# SCH_M5_GreenHat_Coil_Driver_2021-08-27.net
KiCad netlist of a schematic drawn in EasyEDA
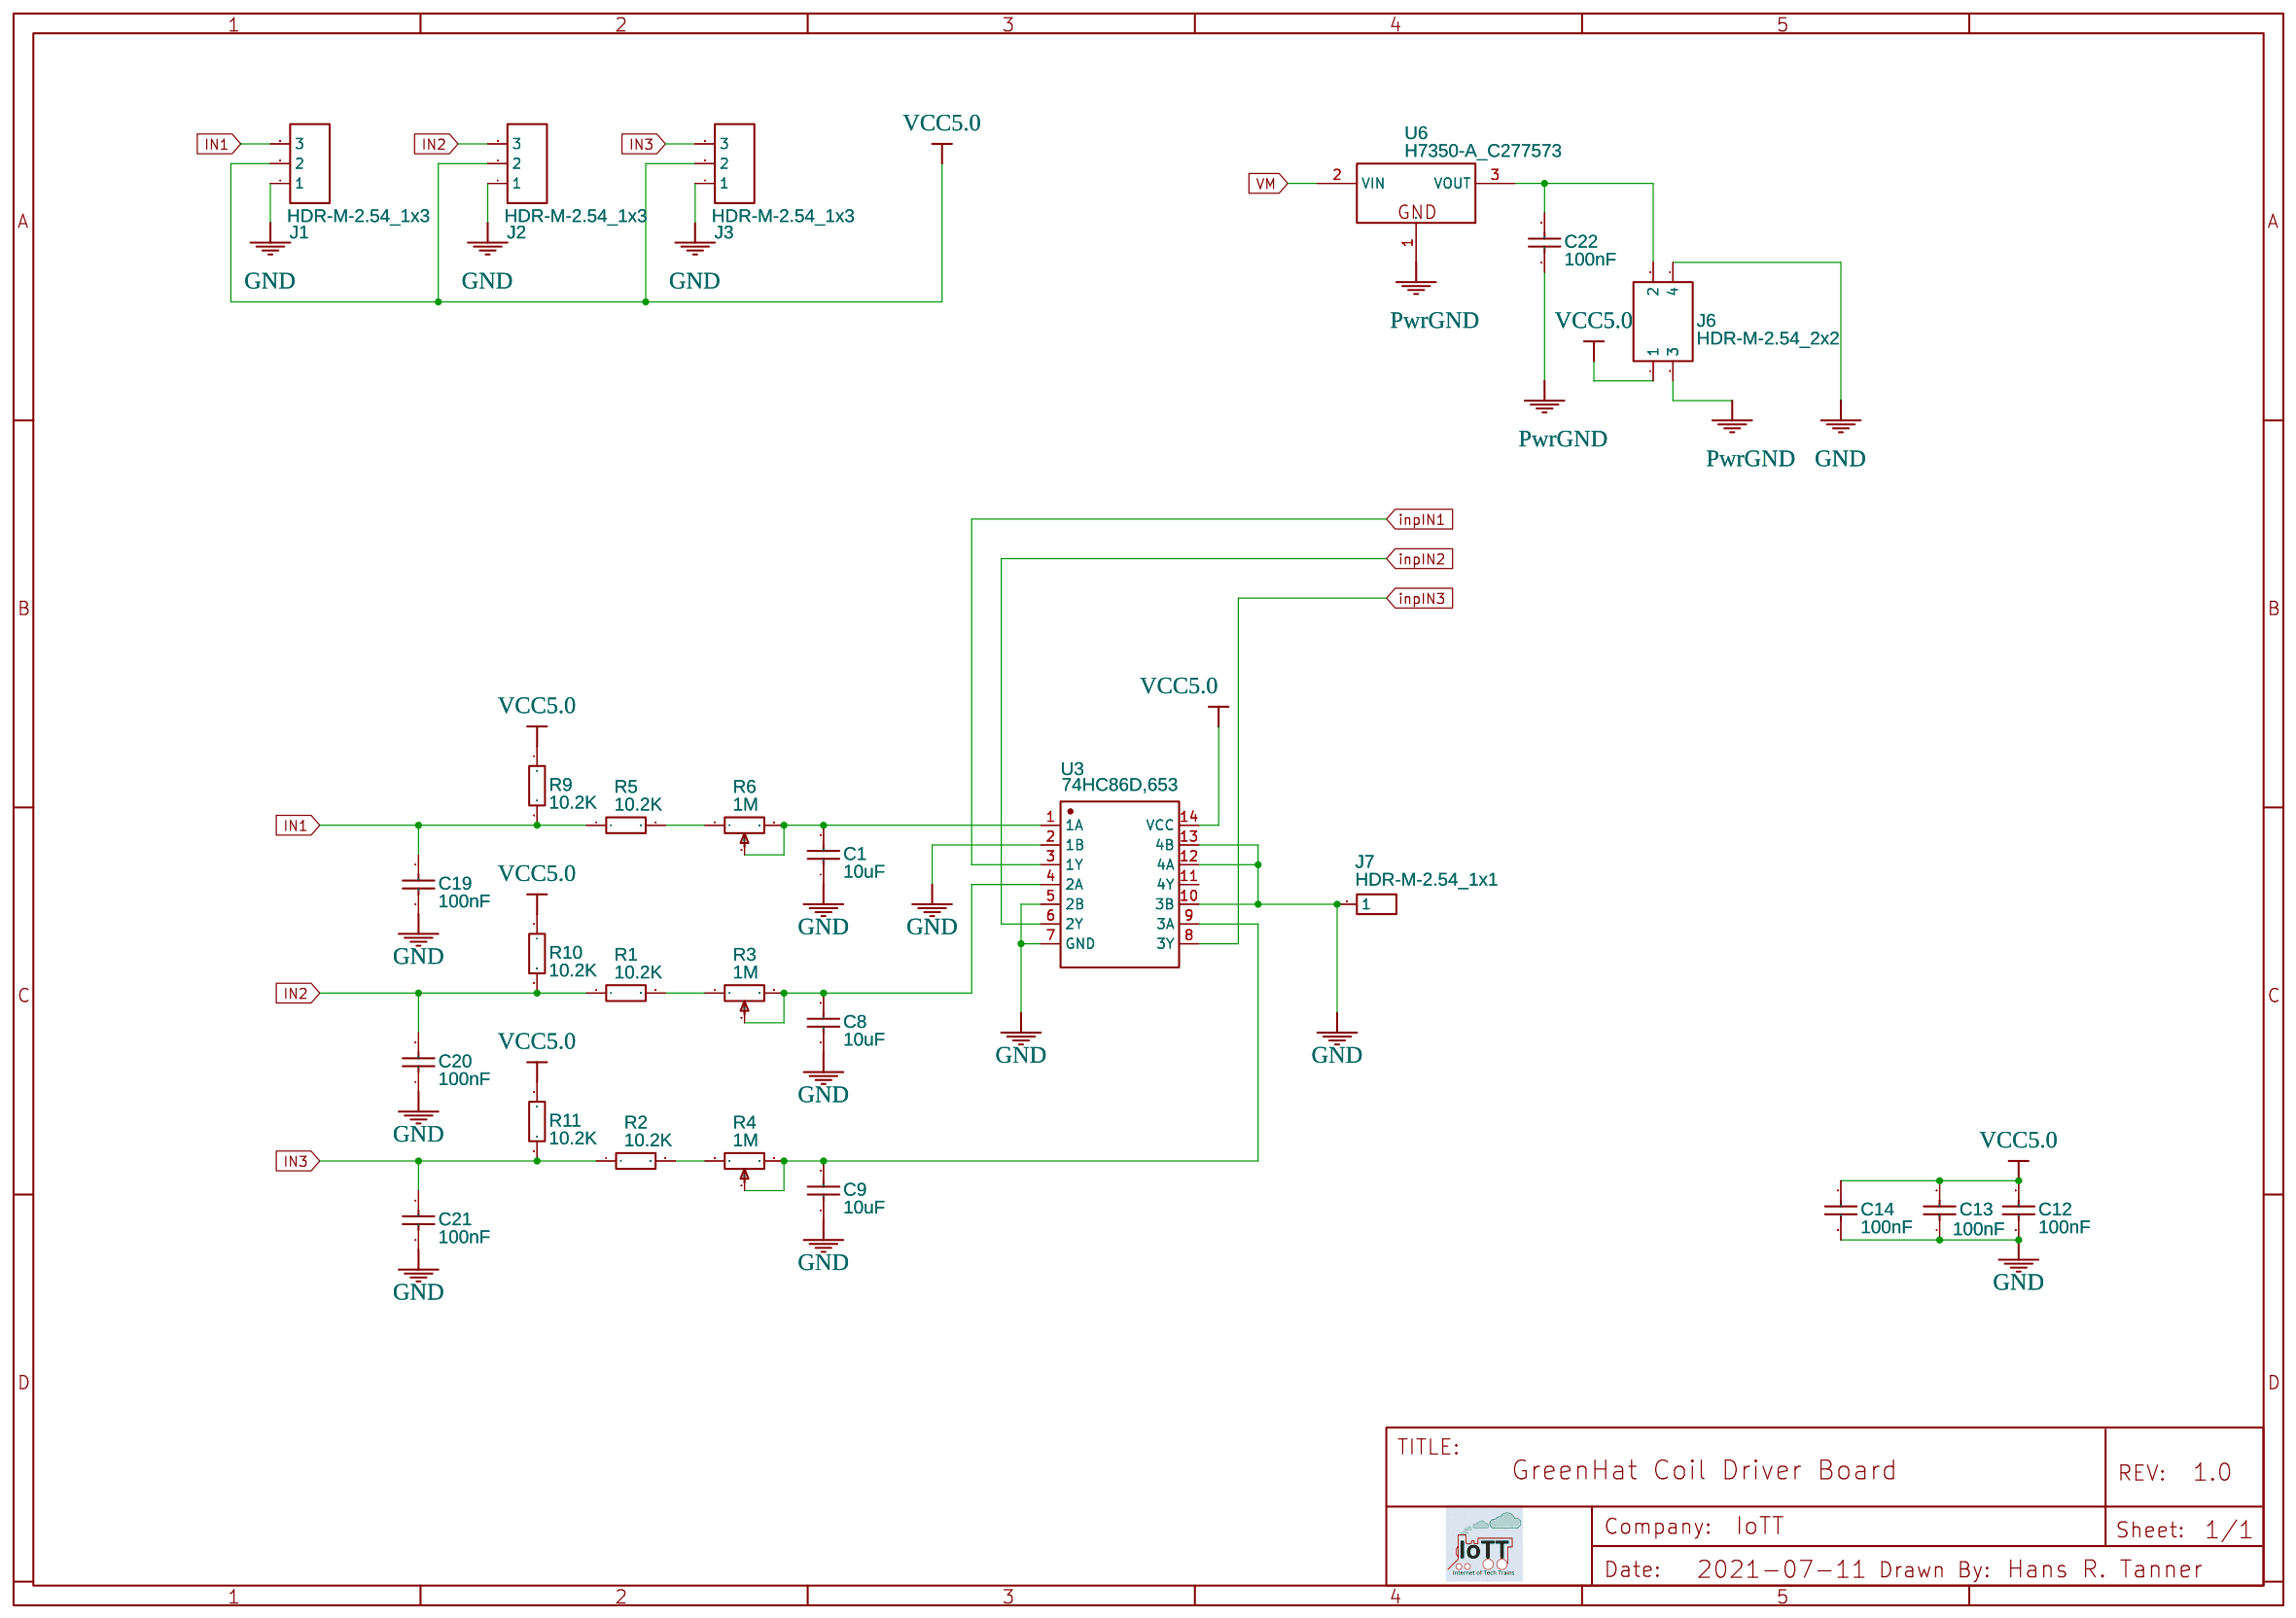
[diagram p0: Input Logic]
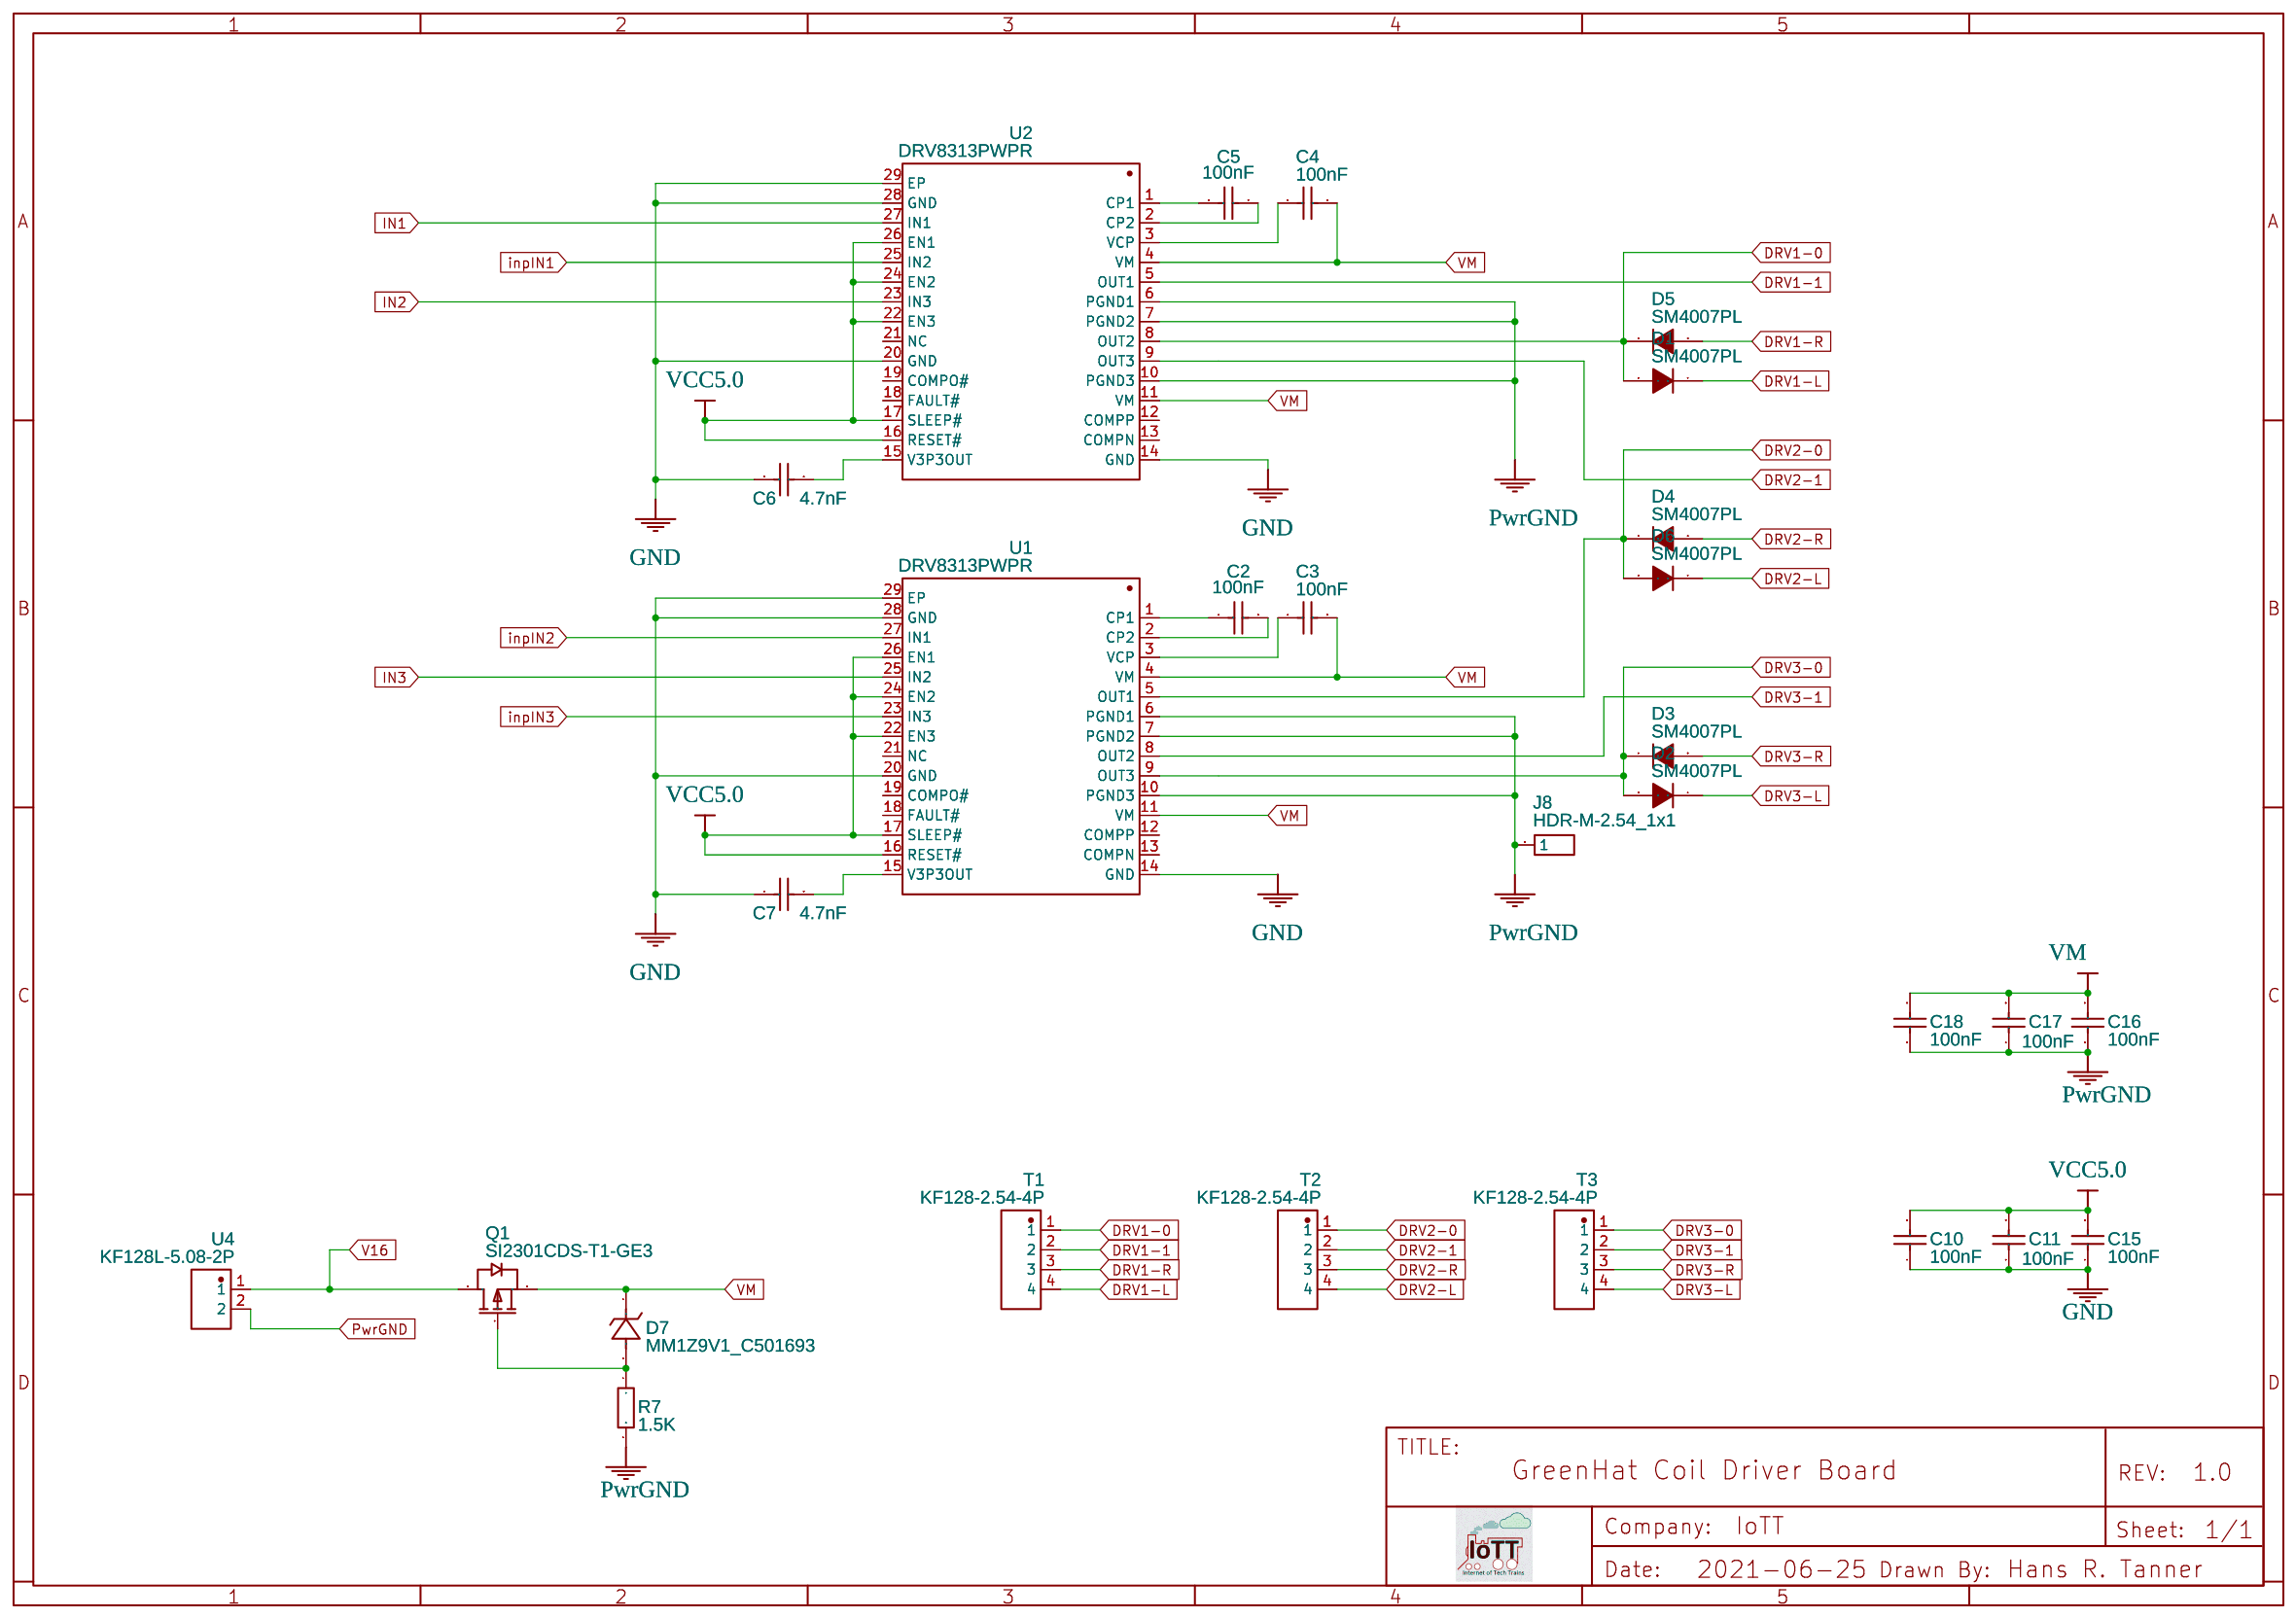
[diagram p1: Bridge]

(export (version "E")
  (design (tool "Eeschema 10.0.6"))
  (components
    (comp (ref "C1")
      (value "10uF")
      (fields
        (field (name "BOM_Manufacturer Part") "CL21A106KAYNNNE")
        (field (name "BOM_Supplier Part") "C15850")
      )
      (libsource (lib "") (part "CL21A106KAYNNNE"))
    )
    (comp (ref "C8")
      (value "10uF")
      (fields
        (field (name "BOM_Manufacturer Part") "CL21A106KAYNNNE")
        (field (name "BOM_Supplier Part") "C15850")
      )
      (libsource (lib "") (part "CL21A106KAYNNNE"))
    )
    (comp (ref "C9")
      (value "10uF")
      (fields
        (field (name "BOM_Manufacturer Part") "CL21A106KAYNNNE")
        (field (name "BOM_Supplier Part") "C15850")
      )
      (libsource (lib "") (part "CL21A106KAYNNNE"))
    )
    (comp (ref "C12")
      (value "100nF")
      (fields
        (field (name "BOM_Manufacturer Part") "CL05B104KO5NNNC")
        (field (name "BOM_Supplier Part") "C1525")
      )
      (libsource (lib "") (part "CL05B104KO5NNNC"))
    )
    (comp (ref "C13")
      (value "100nF")
      (fields
        (field (name "BOM_Manufacturer Part") "CL05B104KO5NNNC")
        (field (name "BOM_Supplier Part") "C1525")
      )
      (libsource (lib "") (part "CL05B104KO5NNNC"))
    )
    (comp (ref "C14")
      (value "100nF")
      (fields
        (field (name "BOM_Manufacturer Part") "CL05B104KO5NNNC")
        (field (name "BOM_Supplier Part") "C1525")
      )
      (libsource (lib "") (part "CL05B104KO5NNNC"))
    )
    (comp (ref "C19")
      (value "100nF")
      (fields
        (field (name "BOM_Manufacturer Part") "CL05B104KO5NNNC")
        (field (name "BOM_Supplier Part") "C1525")
      )
      (libsource (lib "") (part "CL05B104KO5NNNC"))
    )
    (comp (ref "C20")
      (value "100nF")
      (fields
        (field (name "BOM_Manufacturer Part") "CL05B104KO5NNNC")
        (field (name "BOM_Supplier Part") "C1525")
      )
      (libsource (lib "") (part "CL05B104KO5NNNC"))
    )
    (comp (ref "C21")
      (value "100nF")
      (fields
        (field (name "BOM_Manufacturer Part") "CL05B104KO5NNNC")
        (field (name "BOM_Supplier Part") "C1525")
      )
      (libsource (lib "") (part "CL05B104KO5NNNC"))
    )
    (comp (ref "C22")
      (value "100nF")
      (fields
        (field (name "BOM_Manufacturer Part") "CL05B104KO5NNNC")
        (field (name "BOM_Supplier Part") "C1525")
      )
      (libsource (lib "") (part "CL05B104KO5NNNC"))
    )
    (comp (ref "J1")
      (value "HDR-M-2.54_1x3")
      (fields (field (name "BOM_Supplier Part") "C180248"))
      (libsource (lib "") (part "HDR-M-2.54_1x3"))
    )
    (comp (ref "J2")
      (value "HDR-M-2.54_1x3")
      (fields (field (name "BOM_Supplier Part") "C180248"))
      (libsource (lib "") (part "HDR-M-2.54_1x3"))
    )
    (comp (ref "J3")
      (value "HDR-M-2.54_1x3")
      (fields (field (name "BOM_Supplier Part") "C180248"))
      (libsource (lib "") (part "HDR-M-2.54_1x3"))
    )
    (comp (ref "J6")
      (value "HDR-M-2.54_2x2")
      (fields (field (name "BOM_Supplier Part") "C66690"))
      (libsource (lib "") (part "HDR-M-2.54_2x2"))
    )
    (comp (ref "J7")
      (value "HDR-M-2.54_1x1")
      (fields (field (name "BOM_Supplier Part") "C81276"))
      (libsource (lib "") (part "HDR-M-2.54_1x1"))
    )
    (comp (ref "R1")
      (value "10.2K")
      (fields
        (field (name "BOM_Manufacturer Part") "RTT021022FTH")
        (field (name "BOM_Supplier Part") "C102756")
      )
      (libsource (lib "") (part "RTT021022FTH_1"))
    )
    (comp (ref "R2")
      (value "10.2K")
      (fields
        (field (name "BOM_Manufacturer Part") "RTT021022FTH")
        (field (name "BOM_Supplier Part") "C102756")
      )
      (libsource (lib "") (part "RTT021022FTH_1"))
    )
    (comp (ref "R3")
      (value "1M")
      (fields
        (field (name "BOM_Manufacturer Part") "3386P-1-105")
        (field (name "BOM_Supplier Part") "C118946")
      )
      (libsource (lib "") (part "3386P-1-105_C118946"))
    )
    (comp (ref "R4")
      (value "1M")
      (fields
        (field (name "BOM_Manufacturer Part") "3386P-1-105")
        (field (name "BOM_Supplier Part") "C118946")
      )
      (libsource (lib "") (part "3386P-1-105_C118946"))
    )
    (comp (ref "R5")
      (value "10.2K")
      (fields
        (field (name "BOM_Manufacturer Part") "RTT021022FTH")
        (field (name "BOM_Supplier Part") "C102756")
      )
      (libsource (lib "") (part "RTT021022FTH_1"))
    )
    (comp (ref "R6")
      (value "1M")
      (fields
        (field (name "BOM_Manufacturer Part") "3386P-1-105")
        (field (name "BOM_Supplier Part") "C118946")
      )
      (libsource (lib "") (part "3386P-1-105_C118946"))
    )
    (comp (ref "R9")
      (value "10.2K")
      (fields
        (field (name "BOM_Manufacturer Part") "RTT021022FTH")
        (field (name "BOM_Supplier Part") "C102756")
      )
      (libsource (lib "") (part "RTT021022FTH"))
    )
    (comp (ref "R10")
      (value "10.2K")
      (fields
        (field (name "BOM_Manufacturer Part") "RTT021022FTH")
        (field (name "BOM_Supplier Part") "C102756")
      )
      (libsource (lib "") (part "RTT021022FTH"))
    )
    (comp (ref "R11")
      (value "10.2K")
      (fields
        (field (name "BOM_Manufacturer Part") "RTT021022FTH")
        (field (name "BOM_Supplier Part") "C102756")
      )
      (libsource (lib "") (part "RTT021022FTH"))
    )
    (comp (ref "U3")
      (value "74HC86D,653")
      (fields (field (name "BOM_Supplier Part") "C5955"))
      (libsource (lib "") (part "74HC86D,653"))
    )
    (comp (ref "U6")
      (value "H7350-A_C277573")
      (fields (field (name "BOM_Manufacturer Part") "H7350-A") (field (name "BOM_Supplier Part") "C277573"))
      (libsource (lib "") (part "H7350-A_C277573"))
    )
    (comp (ref "C2")
      (value "100nF")
      (fields
        (field (name "BOM_Manufacturer Part") "CL05B104KO5NNNC")
        (field (name "BOM_Supplier Part") "C1525")
      )
      (libsource (lib "") (part "CL05B104KO5NNNC"))
    )
    (comp (ref "C3")
      (value "100nF")
      (fields
        (field (name "BOM_Manufacturer Part") "CL05B104KO5NNNC")
        (field (name "BOM_Supplier Part") "C1525")
      )
      (libsource (lib "") (part "CL05B104KO5NNNC"))
    )
    (comp (ref "C4")
      (value "100nF")
      (fields
        (field (name "BOM_Manufacturer Part") "CL05B104KO5NNNC")
        (field (name "BOM_Supplier Part") "C1525")
      )
      (libsource (lib "") (part "CL05B104KO5NNNC"))
    )
    (comp (ref "C5")
      (value "100nF")
      (fields
        (field (name "BOM_Manufacturer Part") "CL05B104KO5NNNC")
        (field (name "BOM_Supplier Part") "C1525")
      )
      (libsource (lib "") (part "CL05B104KO5NNNC"))
    )
    (comp (ref "C6")
      (value "4.7nF")
      (fields
        (field (name "BOM_Manufacturer Part") "0402B472K500NT")
        (field (name "BOM_Supplier Part") "C1538")
      )
      (libsource (lib "") (part "0402B472K500NT"))
    )
    (comp (ref "C7")
      (value "4.7nF")
      (fields
        (field (name "BOM_Manufacturer Part") "0402B472K500NT")
        (field (name "BOM_Supplier Part") "C1538")
      )
      (libsource (lib "") (part "0402B472K500NT"))
    )
    (comp (ref "C10")
      (value "100nF")
      (fields
        (field (name "BOM_Manufacturer Part") "CL05B104KO5NNNC")
        (field (name "BOM_Supplier Part") "C1525")
      )
      (libsource (lib "") (part "CL05B104KO5NNNC_1"))
    )
    (comp (ref "C11")
      (value "100nF")
      (fields
        (field (name "BOM_Manufacturer Part") "CL05B104KO5NNNC")
        (field (name "BOM_Supplier Part") "C1525")
      )
      (libsource (lib "") (part "CL05B104KO5NNNC_1"))
    )
    (comp (ref "C15")
      (value "100nF")
      (fields
        (field (name "BOM_Manufacturer Part") "CL05B104KO5NNNC")
        (field (name "BOM_Supplier Part") "C1525")
      )
      (libsource (lib "") (part "CL05B104KO5NNNC_1"))
    )
    (comp (ref "C16")
      (value "100nF")
      (fields
        (field (name "BOM_Manufacturer Part") "CL05B104KO5NNNC")
        (field (name "BOM_Supplier Part") "C1525")
      )
      (libsource (lib "") (part "CL05B104KO5NNNC_1"))
    )
    (comp (ref "C17")
      (value "100nF")
      (fields
        (field (name "BOM_Manufacturer Part") "CL05B104KO5NNNC")
        (field (name "BOM_Supplier Part") "C1525")
      )
      (libsource (lib "") (part "CL05B104KO5NNNC_1"))
    )
    (comp (ref "C18")
      (value "100nF")
      (fields
        (field (name "BOM_Manufacturer Part") "CL05B104KO5NNNC")
        (field (name "BOM_Supplier Part") "C1525")
      )
      (libsource (lib "") (part "CL05B104KO5NNNC_1"))
    )
    (comp (ref "D1")
      (value "SM4007PL")
      (fields (field (name "BOM_Supplier Part") "C64898"))
      (libsource (lib "") (part "SM4007PL_1"))
    )
    (comp (ref "D2")
      (value "SM4007PL")
      (fields (field (name "BOM_Supplier Part") "C64898"))
      (libsource (lib "") (part "SM4007PL_1"))
    )
    (comp (ref "D3")
      (value "SM4007PL")
      (fields (field (name "BOM_Supplier Part") "C64898"))
      (libsource (lib "") (part "SM4007PL"))
    )
    (comp (ref "D4")
      (value "SM4007PL")
      (fields (field (name "BOM_Supplier Part") "C64898"))
      (libsource (lib "") (part "SM4007PL"))
    )
    (comp (ref "D5")
      (value "SM4007PL")
      (fields (field (name "BOM_Supplier Part") "C64898"))
      (libsource (lib "") (part "SM4007PL"))
    )
    (comp (ref "D6")
      (value "SM4007PL")
      (fields (field (name "BOM_Supplier Part") "C64898"))
      (libsource (lib "") (part "SM4007PL_1"))
    )
    (comp (ref "D7")
      (value "MM1Z9V1_C501693")
      (fields (field (name "BOM_Manufacturer Part") "MM1Z9V1") (field (name "BOM_Supplier Part") "C501693"))
      (libsource (lib "") (part "MM1Z9V1_C501693"))
    )
    (comp (ref "J8")
      (value "HDR-M-2.54_1x1")
      (fields (field (name "BOM_Supplier Part") "C81276"))
      (libsource (lib "") (part "HDR-M-2.54_1x1"))
    )
    (comp (ref "Q1")
      (value "SI2301CDS-T1-GE3")
      (fields (field (name "BOM_Supplier Part") "C10487"))
      (libsource (lib "") (part "SI2301CDS-T1-GE3"))
    )
    (comp (ref "R7")
      (value "1.5K")
      (fields
        (field (name "BOM_Manufacturer Part") "0402WGF1501TCE")
        (field (name "BOM_Supplier Part") "C25867")
      )
      (libsource (lib "") (part "0402WGF1501TCE"))
    )
    (comp (ref "T1")
      (value "KF128-2.54-4P")
      (fields (field (name "BOM_Supplier Part") "C474922"))
      (libsource (lib "") (part "KF128-2.54-4P"))
    )
    (comp (ref "T2")
      (value "KF128-2.54-4P")
      (fields (field (name "BOM_Supplier Part") "C474922"))
      (libsource (lib "") (part "KF128-2.54-4P"))
    )
    (comp (ref "T3")
      (value "KF128-2.54-4P")
      (fields (field (name "BOM_Supplier Part") "C474922"))
      (libsource (lib "") (part "KF128-2.54-4P"))
    )
    (comp (ref "U1")
      (value "DRV8313PWPR")
      (fields (field (name "BOM_Supplier Part") "C92482"))
      (libsource (lib "") (part "DRV8313PWPR"))
    )
    (comp (ref "U2")
      (value "DRV8313PWPR")
      (fields (field (name "BOM_Supplier Part") "C92482"))
      (libsource (lib "") (part "DRV8313PWPR"))
    )
    (comp (ref "U4")
      (value "KF128L-5.08-2P")
      (fields (field (name "BOM_Supplier Part") "C474940"))
      (libsource (lib "") (part "KF128L-5.08-2P"))
    )
  )
  (nets
    (net (code "1") (name "DRV1-0") (class "Default")
      (node (ref "D1") (pin "2") (pinfunction "A_2") (pintype "unspecified"))
      (node (ref "D5") (pin "1") (pinfunction "C_1") (pintype "unspecified"))
      (node (ref "T1") (pin "1") (pinfunction "1_1") (pintype "unspecified"))
      (node (ref "U2") (pin "8") (pinfunction "OUT2_8") (pintype "unspecified"))
    )
    (net (code "2") (name "DRV1-1") (class "Default")
      (node (ref "T1") (pin "2") (pinfunction "2_2") (pintype "unspecified"))
      (node (ref "U2") (pin "5") (pinfunction "OUT1_5") (pintype "unspecified"))
    )
    (net (code "3") (name "DRV1-L") (class "Default")
      (node (ref "D1") (pin "1") (pinfunction "C_1") (pintype "unspecified"))
      (node (ref "T1") (pin "4") (pinfunction "4_4") (pintype "unspecified"))
    )
    (net (code "4") (name "DRV1-R") (class "Default")
      (node (ref "D5") (pin "2") (pinfunction "A_2") (pintype "unspecified"))
      (node (ref "T1") (pin "3") (pinfunction "3_3") (pintype "unspecified"))
    )
    (net (code "5") (name "DRV2-0") (class "Default")
      (node (ref "D4") (pin "1") (pinfunction "C_1") (pintype "unspecified"))
      (node (ref "D6") (pin "2") (pinfunction "A_2") (pintype "unspecified"))
      (node (ref "T2") (pin "1") (pinfunction "1_1") (pintype "unspecified"))
      (node (ref "U1") (pin "5") (pinfunction "OUT1_5") (pintype "unspecified"))
    )
    (net (code "6") (name "DRV2-1") (class "Default")
      (node (ref "T2") (pin "2") (pinfunction "2_2") (pintype "unspecified"))
      (node (ref "U2") (pin "9") (pinfunction "OUT3_9") (pintype "unspecified"))
    )
    (net (code "7") (name "DRV2-L") (class "Default")
      (node (ref "D6") (pin "1") (pinfunction "C_1") (pintype "unspecified"))
      (node (ref "T2") (pin "4") (pinfunction "4_4") (pintype "unspecified"))
    )
    (net (code "8") (name "DRV2-R") (class "Default")
      (node (ref "D4") (pin "2") (pinfunction "A_2") (pintype "unspecified"))
      (node (ref "T2") (pin "3") (pinfunction "3_3") (pintype "unspecified"))
    )
    (net (code "9") (name "DRV3-0") (class "Default")
      (node (ref "D2") (pin "2") (pinfunction "A_2") (pintype "unspecified"))
      (node (ref "D3") (pin "1") (pinfunction "C_1") (pintype "unspecified"))
      (node (ref "T3") (pin "1") (pinfunction "1_1") (pintype "unspecified"))
      (node (ref "U1") (pin "9") (pinfunction "OUT3_9") (pintype "unspecified"))
    )
    (net (code "10") (name "DRV3-1") (class "Default")
      (node (ref "T3") (pin "2") (pinfunction "2_2") (pintype "unspecified"))
      (node (ref "U1") (pin "8") (pinfunction "OUT2_8") (pintype "unspecified"))
    )
    (net (code "11") (name "DRV3-L") (class "Default")
      (node (ref "D2") (pin "1") (pinfunction "C_1") (pintype "unspecified"))
      (node (ref "T3") (pin "4") (pinfunction "4_4") (pintype "unspecified"))
    )
    (net (code "12") (name "DRV3-R") (class "Default")
      (node (ref "D3") (pin "2") (pinfunction "A_2") (pintype "unspecified"))
      (node (ref "T3") (pin "3") (pinfunction "3_3") (pintype "unspecified"))
    )
    (net (code "13") (name "GND") (class "Default")
      (node (ref "C1") (pin "1") (pinfunction "1_1") (pintype "input"))
      (node (ref "C10") (pin "1") (pinfunction "1_1") (pintype "input"))
      (node (ref "C11") (pin "1") (pinfunction "1_1") (pintype "input"))
      (node (ref "C12") (pin "1") (pinfunction "1_1") (pintype "input"))
      (node (ref "C13") (pin "1") (pinfunction "1_1") (pintype "input"))
      (node (ref "C14") (pin "1") (pinfunction "1_1") (pintype "input"))
      (node (ref "C15") (pin "1") (pinfunction "1_1") (pintype "input"))
      (node (ref "C19") (pin "1") (pinfunction "1_1") (pintype "input"))
      (node (ref "C20") (pin "1") (pinfunction "1_1") (pintype "input"))
      (node (ref "C21") (pin "1") (pinfunction "1_1") (pintype "input"))
      (node (ref "C6") (pin "1") (pinfunction "1_1") (pintype "input"))
      (node (ref "C7") (pin "1") (pinfunction "1_1") (pintype "input"))
      (node (ref "C8") (pin "1") (pinfunction "1_1") (pintype "input"))
      (node (ref "C9") (pin "1") (pinfunction "1_1") (pintype "input"))
      (node (ref "J1") (pin "1") (pinfunction "1_1") (pintype "input"))
      (node (ref "J2") (pin "1") (pinfunction "1_1") (pintype "input"))
      (node (ref "J3") (pin "1") (pinfunction "1_1") (pintype "input"))
      (node (ref "J6") (pin "4") (pinfunction "4_4") (pintype "input"))
      (node (ref "J7") (pin "1") (pinfunction "1_1") (pintype "input"))
      (node (ref "U1") (pin "14") (pinfunction "GND_14") (pintype "unspecified"))
      (node (ref "U1") (pin "20") (pinfunction "GND_20") (pintype "unspecified"))
      (node (ref "U1") (pin "28") (pinfunction "GND_28") (pintype "unspecified"))
      (node (ref "U1") (pin "29") (pinfunction "EP_29") (pintype "unspecified"))
      (node (ref "U2") (pin "14") (pinfunction "GND_14") (pintype "unspecified"))
      (node (ref "U2") (pin "20") (pinfunction "GND_20") (pintype "unspecified"))
      (node (ref "U2") (pin "28") (pinfunction "GND_28") (pintype "unspecified"))
      (node (ref "U2") (pin "29") (pinfunction "EP_29") (pintype "unspecified"))
      (node (ref "U3") (pin "10") (pinfunction "3B_10") (pintype "unspecified"))
      (node (ref "U3") (pin "12") (pinfunction "4A_12") (pintype "unspecified"))
      (node (ref "U3") (pin "13") (pinfunction "4B_13") (pintype "unspecified"))
      (node (ref "U3") (pin "2") (pinfunction "1B_2") (pintype "unspecified"))
      (node (ref "U3") (pin "5") (pinfunction "2B_5") (pintype "unspecified"))
      (node (ref "U3") (pin "7") (pinfunction "GND_7") (pintype "unspecified"))
    )
    (net (code "14") (name "IN1") (class "Default")
      (node (ref "C19") (pin "2") (pinfunction "2_2") (pintype "input"))
      (node (ref "J1") (pin "3") (pinfunction "3_3") (pintype "input"))
      (node (ref "R5") (pin "1") (pinfunction "1_1") (pintype "input"))
      (node (ref "R9") (pin "2") (pinfunction "2_2") (pintype "input"))
      (node (ref "U2") (pin "27") (pinfunction "IN1_27") (pintype "unspecified"))
    )
    (net (code "15") (name "IN2") (class "Default")
      (node (ref "C20") (pin "2") (pinfunction "2_2") (pintype "input"))
      (node (ref "J2") (pin "3") (pinfunction "3_3") (pintype "input"))
      (node (ref "R1") (pin "1") (pinfunction "1_1") (pintype "input"))
      (node (ref "R10") (pin "2") (pinfunction "2_2") (pintype "input"))
      (node (ref "U2") (pin "23") (pinfunction "IN3_23") (pintype "unspecified"))
    )
    (net (code "16") (name "IN3") (class "Default")
      (node (ref "C21") (pin "2") (pinfunction "2_2") (pintype "input"))
      (node (ref "J3") (pin "3") (pinfunction "3_3") (pintype "input"))
      (node (ref "R11") (pin "2") (pinfunction "2_2") (pintype "input"))
      (node (ref "R2") (pin "1") (pinfunction "1_1") (pintype "input"))
      (node (ref "U1") (pin "25") (pinfunction "IN2_25") (pintype "unspecified"))
    )
    (net (code "17") (name "Net-(D7-A)") (class "Default")
      (node (ref "D7") (pin "2") (pinfunction "A_2") (pintype "unspecified"))
      (node (ref "Q1") (pin "1") (pinfunction "G_1") (pintype "unspecified"))
      (node (ref "R7") (pin "1") (pinfunction "1_1") (pintype "input"))
    )
    (net (code "18") (name "Net-(R1-Pad2)") (class "Default")
      (node (ref "R1") (pin "2") (pinfunction "2_2") (pintype "input"))
      (node (ref "R3") (pin "1") (pinfunction "1_1") (pintype "input"))
    )
    (net (code "19") (name "Net-(R2-Pad2)") (class "Default")
      (node (ref "R2") (pin "2") (pinfunction "2_2") (pintype "input"))
      (node (ref "R4") (pin "1") (pinfunction "1_1") (pintype "input"))
    )
    (net (code "20") (name "Net-(R5-Pad2)") (class "Default")
      (node (ref "R5") (pin "2") (pinfunction "2_2") (pintype "input"))
      (node (ref "R6") (pin "1") (pinfunction "1_1") (pintype "input"))
    )
    (net (code "21") (name "Net-(U1-CP1)") (class "Default")
      (node (ref "C2") (pin "1") (pinfunction "1_1") (pintype "input"))
      (node (ref "U1") (pin "1") (pinfunction "CP1_1") (pintype "unspecified"))
    )
    (net (code "22") (name "Net-(U1-CP2)") (class "Default")
      (node (ref "C2") (pin "2") (pinfunction "2_2") (pintype "input"))
      (node (ref "U1") (pin "2") (pinfunction "CP2_2") (pintype "unspecified"))
    )
    (net (code "23") (name "Net-(U1-V3P3OUT)") (class "Default")
      (node (ref "C7") (pin "2") (pinfunction "2_2") (pintype "input"))
      (node (ref "U1") (pin "15") (pinfunction "V3P3OUT_15") (pintype "unspecified"))
    )
    (net (code "24") (name "Net-(U1-VCP)") (class "Default")
      (node (ref "C3") (pin "1") (pinfunction "1_1") (pintype "input"))
      (node (ref "U1") (pin "3") (pinfunction "VCP_3") (pintype "unspecified"))
    )
    (net (code "25") (name "Net-(U2-CP1)") (class "Default")
      (node (ref "C5") (pin "1") (pinfunction "1_1") (pintype "input"))
      (node (ref "U2") (pin "1") (pinfunction "CP1_1") (pintype "unspecified"))
    )
    (net (code "26") (name "Net-(U2-CP2)") (class "Default")
      (node (ref "C5") (pin "2") (pinfunction "2_2") (pintype "input"))
      (node (ref "U2") (pin "2") (pinfunction "CP2_2") (pintype "unspecified"))
    )
    (net (code "27") (name "Net-(U2-V3P3OUT)") (class "Default")
      (node (ref "C6") (pin "2") (pinfunction "2_2") (pintype "input"))
      (node (ref "U2") (pin "15") (pinfunction "V3P3OUT_15") (pintype "unspecified"))
    )
    (net (code "28") (name "Net-(U2-VCP)") (class "Default")
      (node (ref "C4") (pin "1") (pinfunction "1_1") (pintype "input"))
      (node (ref "U2") (pin "3") (pinfunction "VCP_3") (pintype "unspecified"))
    )
    (net (code "29") (name "Net-(U3-1A)") (class "Default")
      (node (ref "C1") (pin "2") (pinfunction "2_2") (pintype "input"))
      (node (ref "R6") (pin "2") (pinfunction "2_2") (pintype "input"))
      (node (ref "R6") (pin "3") (pinfunction "3_3") (pintype "input"))
      (node (ref "U3") (pin "1") (pinfunction "1A_1") (pintype "unspecified"))
    )
    (net (code "30") (name "Net-(U3-2A)") (class "Default")
      (node (ref "C8") (pin "2") (pinfunction "2_2") (pintype "input"))
      (node (ref "R3") (pin "2") (pinfunction "2_2") (pintype "input"))
      (node (ref "R3") (pin "3") (pinfunction "3_3") (pintype "input"))
      (node (ref "U3") (pin "4") (pinfunction "2A_4") (pintype "unspecified"))
    )
    (net (code "31") (name "Net-(U3-3A)") (class "Default")
      (node (ref "C9") (pin "2") (pinfunction "2_2") (pintype "input"))
      (node (ref "R4") (pin "2") (pinfunction "2_2") (pintype "input"))
      (node (ref "R4") (pin "3") (pinfunction "3_3") (pintype "input"))
      (node (ref "U3") (pin "9") (pinfunction "3A_9") (pintype "unspecified"))
    )
    (net (code "32") (name "Net-(U6-VOUT)") (class "Default")
      (node (ref "C22") (pin "2") (pinfunction "2_2") (pintype "input"))
      (node (ref "J6") (pin "2") (pinfunction "2_2") (pintype "input"))
      (node (ref "U6") (pin "3") (pinfunction "VOUT_3") (pintype "passive"))
    )
    (net (code "33") (name "PwrGND") (class "Default")
      (node (ref "C16") (pin "1") (pinfunction "1_1") (pintype "input"))
      (node (ref "C17") (pin "1") (pinfunction "1_1") (pintype "input"))
      (node (ref "C18") (pin "1") (pinfunction "1_1") (pintype "input"))
      (node (ref "C22") (pin "1") (pinfunction "1_1") (pintype "input"))
      (node (ref "J6") (pin "3") (pinfunction "3_3") (pintype "input"))
      (node (ref "J8") (pin "1") (pinfunction "1_1") (pintype "input"))
      (node (ref "R7") (pin "2") (pinfunction "2_2") (pintype "input"))
      (node (ref "U1") (pin "10") (pinfunction "PGND3_10") (pintype "unspecified"))
      (node (ref "U1") (pin "6") (pinfunction "PGND1_6") (pintype "unspecified"))
      (node (ref "U1") (pin "7") (pinfunction "PGND2_7") (pintype "unspecified"))
      (node (ref "U2") (pin "10") (pinfunction "PGND3_10") (pintype "unspecified"))
      (node (ref "U2") (pin "6") (pinfunction "PGND1_6") (pintype "unspecified"))
      (node (ref "U2") (pin "7") (pinfunction "PGND2_7") (pintype "unspecified"))
      (node (ref "U4") (pin "2") (pinfunction "2_2") (pintype "unspecified"))
      (node (ref "U6") (pin "1") (pinfunction "GND_1") (pintype "unspecified"))
    )
    (net (code "34") (name "V16") (class "Default")
      (node (ref "Q1") (pin "3") (pinfunction "D_3") (pintype "unspecified"))
      (node (ref "U4") (pin "1") (pinfunction "1_1") (pintype "unspecified"))
    )
    (net (code "35") (name "VCC5.0") (class "Default")
      (node (ref "C10") (pin "2") (pinfunction "2_2") (pintype "input"))
      (node (ref "C11") (pin "2") (pinfunction "2_2") (pintype "input"))
      (node (ref "C12") (pin "2") (pinfunction "2_2") (pintype "input"))
      (node (ref "C13") (pin "2") (pinfunction "2_2") (pintype "input"))
      (node (ref "C14") (pin "2") (pinfunction "2_2") (pintype "input"))
      (node (ref "C15") (pin "2") (pinfunction "2_2") (pintype "input"))
      (node (ref "J1") (pin "2") (pinfunction "2_2") (pintype "input"))
      (node (ref "J2") (pin "2") (pinfunction "2_2") (pintype "input"))
      (node (ref "J3") (pin "2") (pinfunction "2_2") (pintype "input"))
      (node (ref "J6") (pin "1") (pinfunction "1_1") (pintype "input"))
      (node (ref "R10") (pin "1") (pinfunction "1_1") (pintype "input"))
      (node (ref "R11") (pin "1") (pinfunction "1_1") (pintype "input"))
      (node (ref "R9") (pin "1") (pinfunction "1_1") (pintype "input"))
      (node (ref "U1") (pin "16") (pinfunction "RESET#_16") (pintype "unspecified"))
      (node (ref "U1") (pin "17") (pinfunction "SLEEP#_17") (pintype "unspecified"))
      (node (ref "U1") (pin "22") (pinfunction "EN3_22") (pintype "unspecified"))
      (node (ref "U1") (pin "24") (pinfunction "EN2_24") (pintype "unspecified"))
      (node (ref "U1") (pin "26") (pinfunction "EN1_26") (pintype "unspecified"))
      (node (ref "U2") (pin "16") (pinfunction "RESET#_16") (pintype "unspecified"))
      (node (ref "U2") (pin "17") (pinfunction "SLEEP#_17") (pintype "unspecified"))
      (node (ref "U2") (pin "22") (pinfunction "EN3_22") (pintype "unspecified"))
      (node (ref "U2") (pin "24") (pinfunction "EN2_24") (pintype "unspecified"))
      (node (ref "U2") (pin "26") (pinfunction "EN1_26") (pintype "unspecified"))
      (node (ref "U3") (pin "14") (pinfunction "VCC_14") (pintype "unspecified"))
    )
    (net (code "36") (name "VM") (class "Default")
      (node (ref "C16") (pin "2") (pinfunction "2_2") (pintype "input"))
      (node (ref "C17") (pin "2") (pinfunction "2_2") (pintype "input"))
      (node (ref "C18") (pin "2") (pinfunction "2_2") (pintype "input"))
      (node (ref "C3") (pin "2") (pinfunction "2_2") (pintype "input"))
      (node (ref "C4") (pin "2") (pinfunction "2_2") (pintype "input"))
      (node (ref "D7") (pin "1") (pinfunction "K_1") (pintype "unspecified"))
      (node (ref "Q1") (pin "2") (pinfunction "S_2") (pintype "unspecified"))
      (node (ref "U1") (pin "11") (pinfunction "VM_11") (pintype "unspecified"))
      (node (ref "U1") (pin "4") (pinfunction "VM_4") (pintype "unspecified"))
      (node (ref "U2") (pin "11") (pinfunction "VM_11") (pintype "unspecified"))
      (node (ref "U2") (pin "4") (pinfunction "VM_4") (pintype "unspecified"))
      (node (ref "U6") (pin "2") (pinfunction "VIN_2") (pintype "unspecified"))
    )
    (net (code "37") (name "inpIN1") (class "Default")
      (node (ref "U2") (pin "25") (pinfunction "IN2_25") (pintype "unspecified"))
      (node (ref "U3") (pin "3") (pinfunction "1Y_3") (pintype "unspecified"))
    )
    (net (code "38") (name "inpIN2") (class "Default")
      (node (ref "U1") (pin "27") (pinfunction "IN1_27") (pintype "unspecified"))
      (node (ref "U3") (pin "6") (pinfunction "2Y_6") (pintype "unspecified"))
    )
    (net (code "39") (name "inpIN3") (class "Default")
      (node (ref "U1") (pin "23") (pinfunction "IN3_23") (pintype "unspecified"))
      (node (ref "U3") (pin "8") (pinfunction "3Y_8") (pintype "unspecified"))
    )
    (net (code "40") (name "unconnected-(U1-COMPN-Pad13)") (class "Default")
      (node (ref "U1") (pin "13") (pinfunction "COMPN_13") (pintype "unspecified"))
    )
    (net (code "41") (name "unconnected-(U1-COMPO#-Pad19)") (class "Default")
      (node (ref "U1") (pin "19") (pinfunction "COMPO#_19") (pintype "unspecified"))
    )
    (net (code "42") (name "unconnected-(U1-COMPP-Pad12)") (class "Default")
      (node (ref "U1") (pin "12") (pinfunction "COMPP_12") (pintype "unspecified"))
    )
    (net (code "43") (name "unconnected-(U1-FAULT#-Pad18)") (class "Default")
      (node (ref "U1") (pin "18") (pinfunction "FAULT#_18") (pintype "unspecified"))
    )
    (net (code "44") (name "unconnected-(U1-NC-Pad21)") (class "Default")
      (node (ref "U1") (pin "21") (pinfunction "NC_21") (pintype "unspecified"))
    )
    (net (code "45") (name "unconnected-(U2-COMPN-Pad13)") (class "Default")
      (node (ref "U2") (pin "13") (pinfunction "COMPN_13") (pintype "unspecified"))
    )
    (net (code "46") (name "unconnected-(U2-COMPO#-Pad19)") (class "Default")
      (node (ref "U2") (pin "19") (pinfunction "COMPO#_19") (pintype "unspecified"))
    )
    (net (code "47") (name "unconnected-(U2-COMPP-Pad12)") (class "Default")
      (node (ref "U2") (pin "12") (pinfunction "COMPP_12") (pintype "unspecified"))
    )
    (net (code "48") (name "unconnected-(U2-FAULT#-Pad18)") (class "Default")
      (node (ref "U2") (pin "18") (pinfunction "FAULT#_18") (pintype "unspecified"))
    )
    (net (code "49") (name "unconnected-(U2-NC-Pad21)") (class "Default")
      (node (ref "U2") (pin "21") (pinfunction "NC_21") (pintype "unspecified"))
    )
    (net (code "50") (name "unconnected-(U3-4Y-Pad11)") (class "Default")
      (node (ref "U3") (pin "11") (pinfunction "4Y_11") (pintype "unspecified"))
    )
  )
)
